# FIDO2AUTH_00211.net
KiCad netlist of a schematic drawn in EAGLE
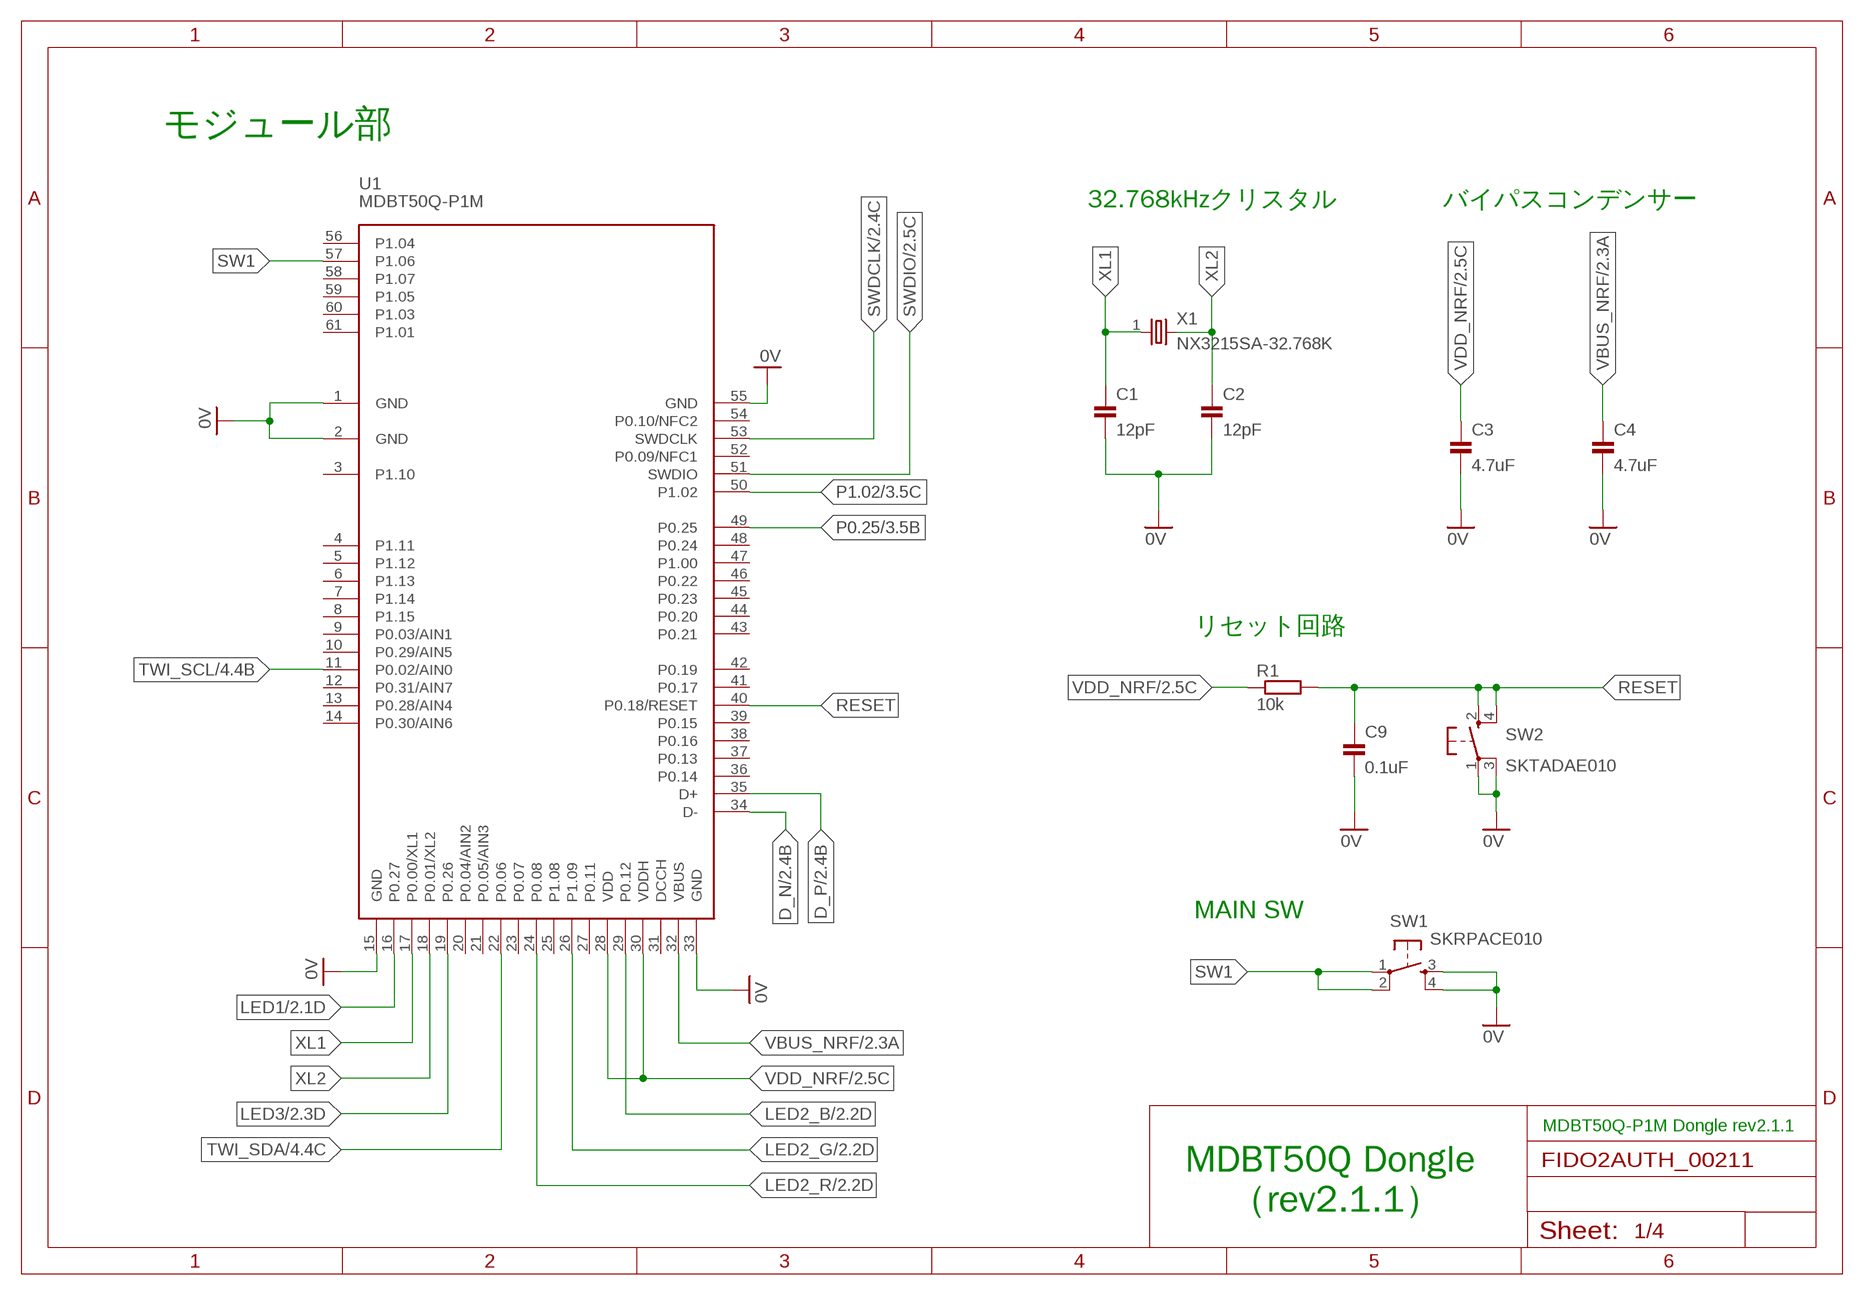
[diagram p0: schematic, sheet 1]
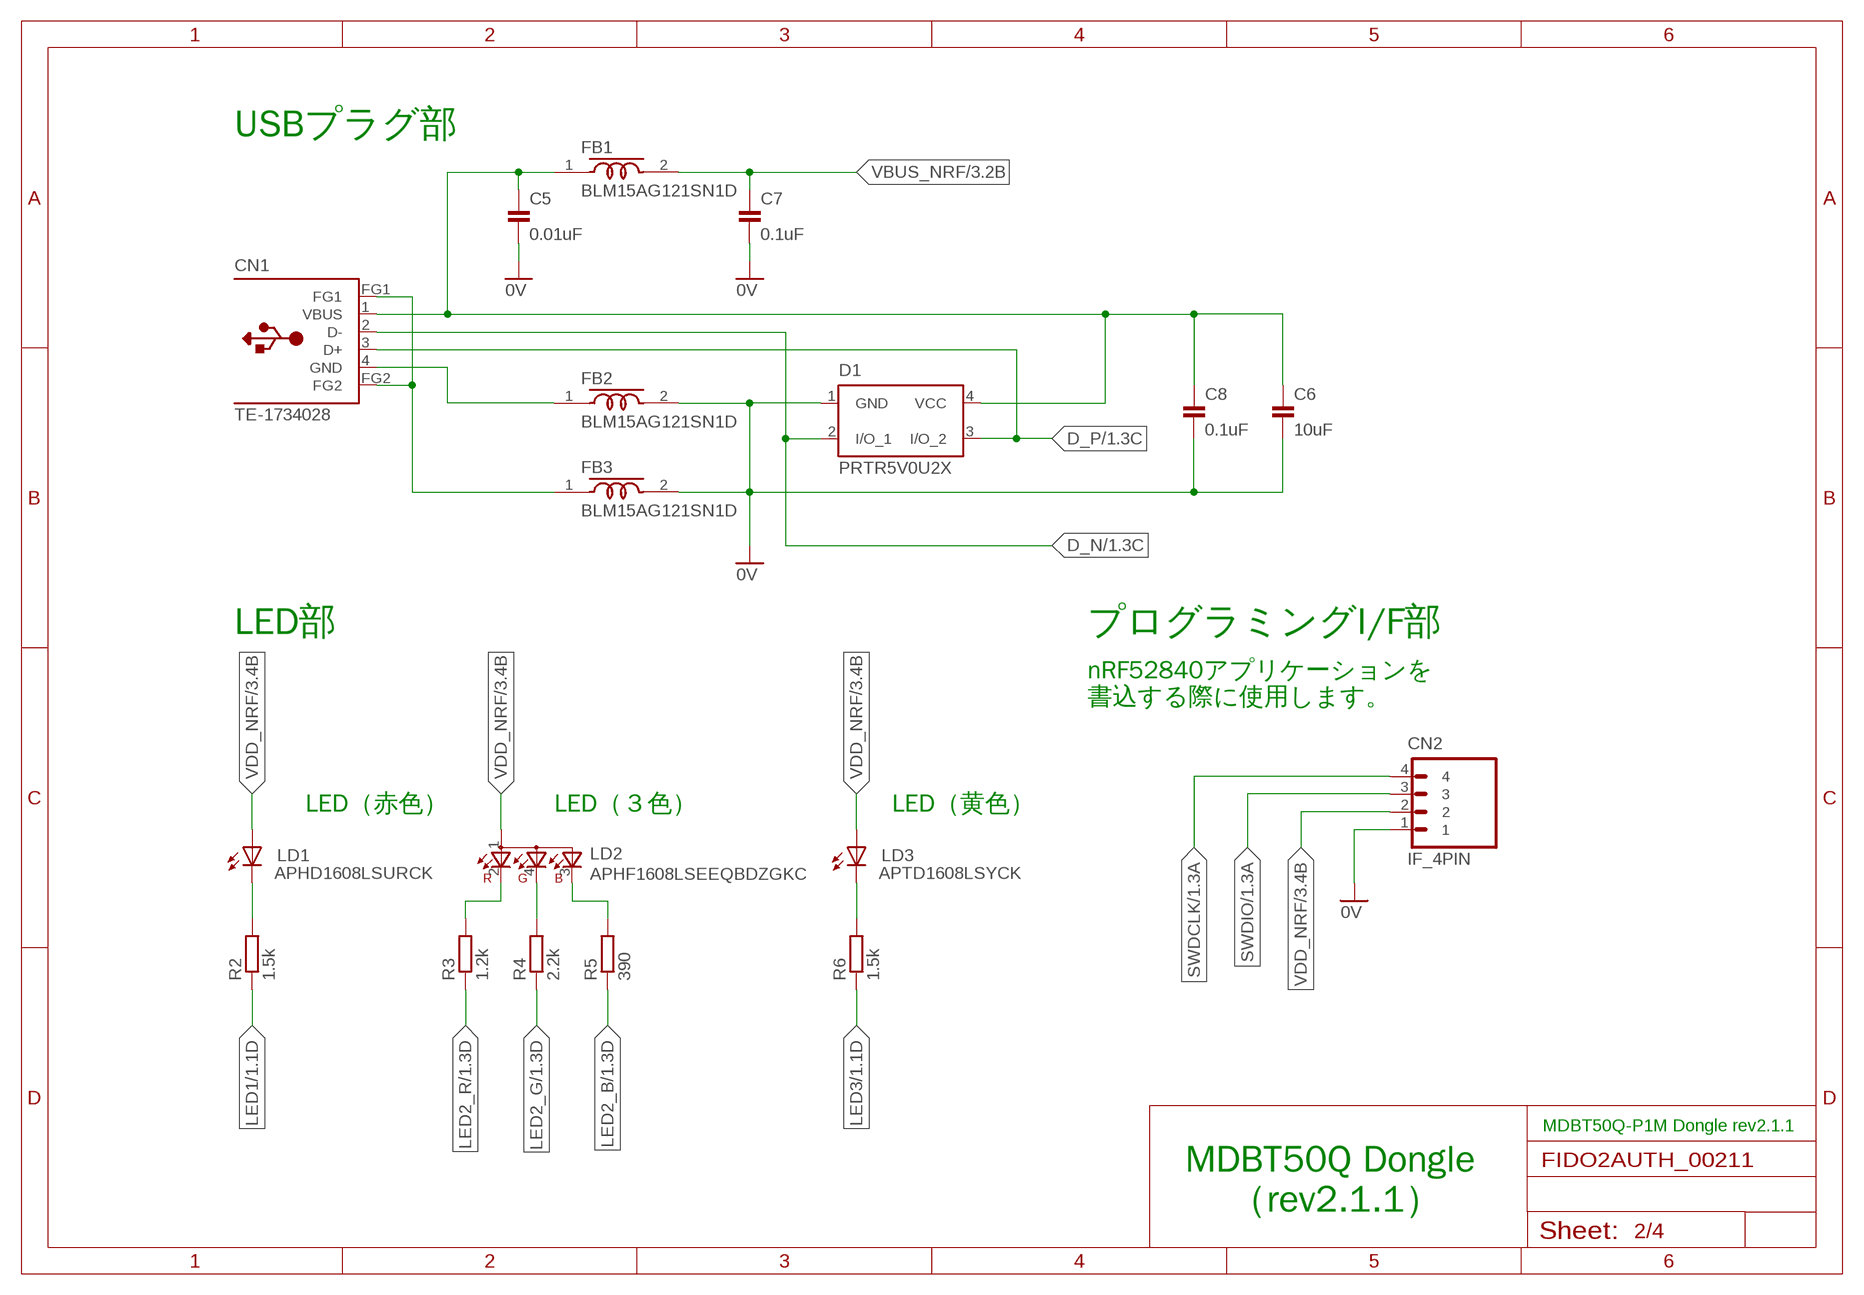
[diagram p1: schematic, sheet 2]
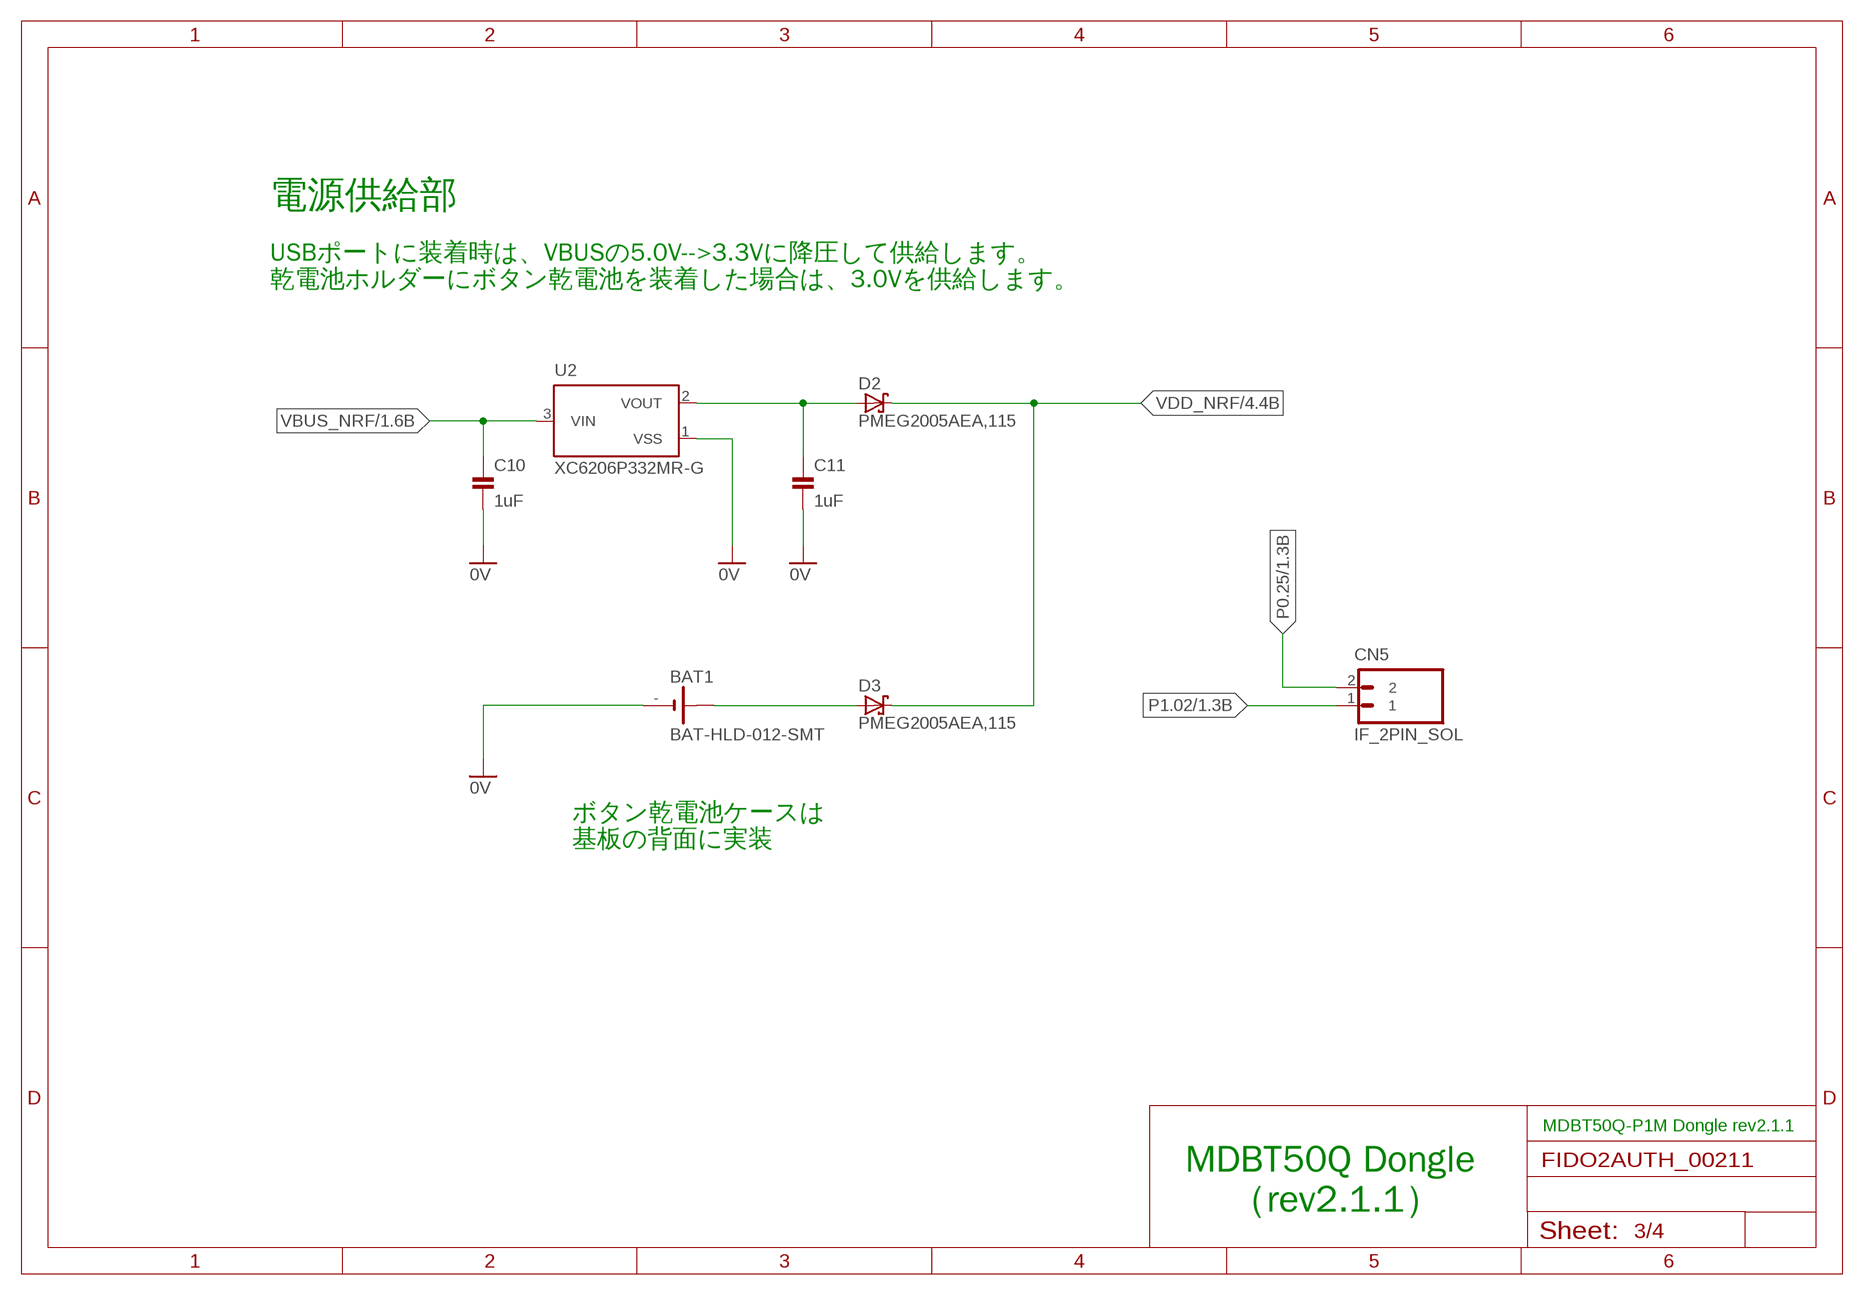
[diagram p2: schematic, sheet 3]
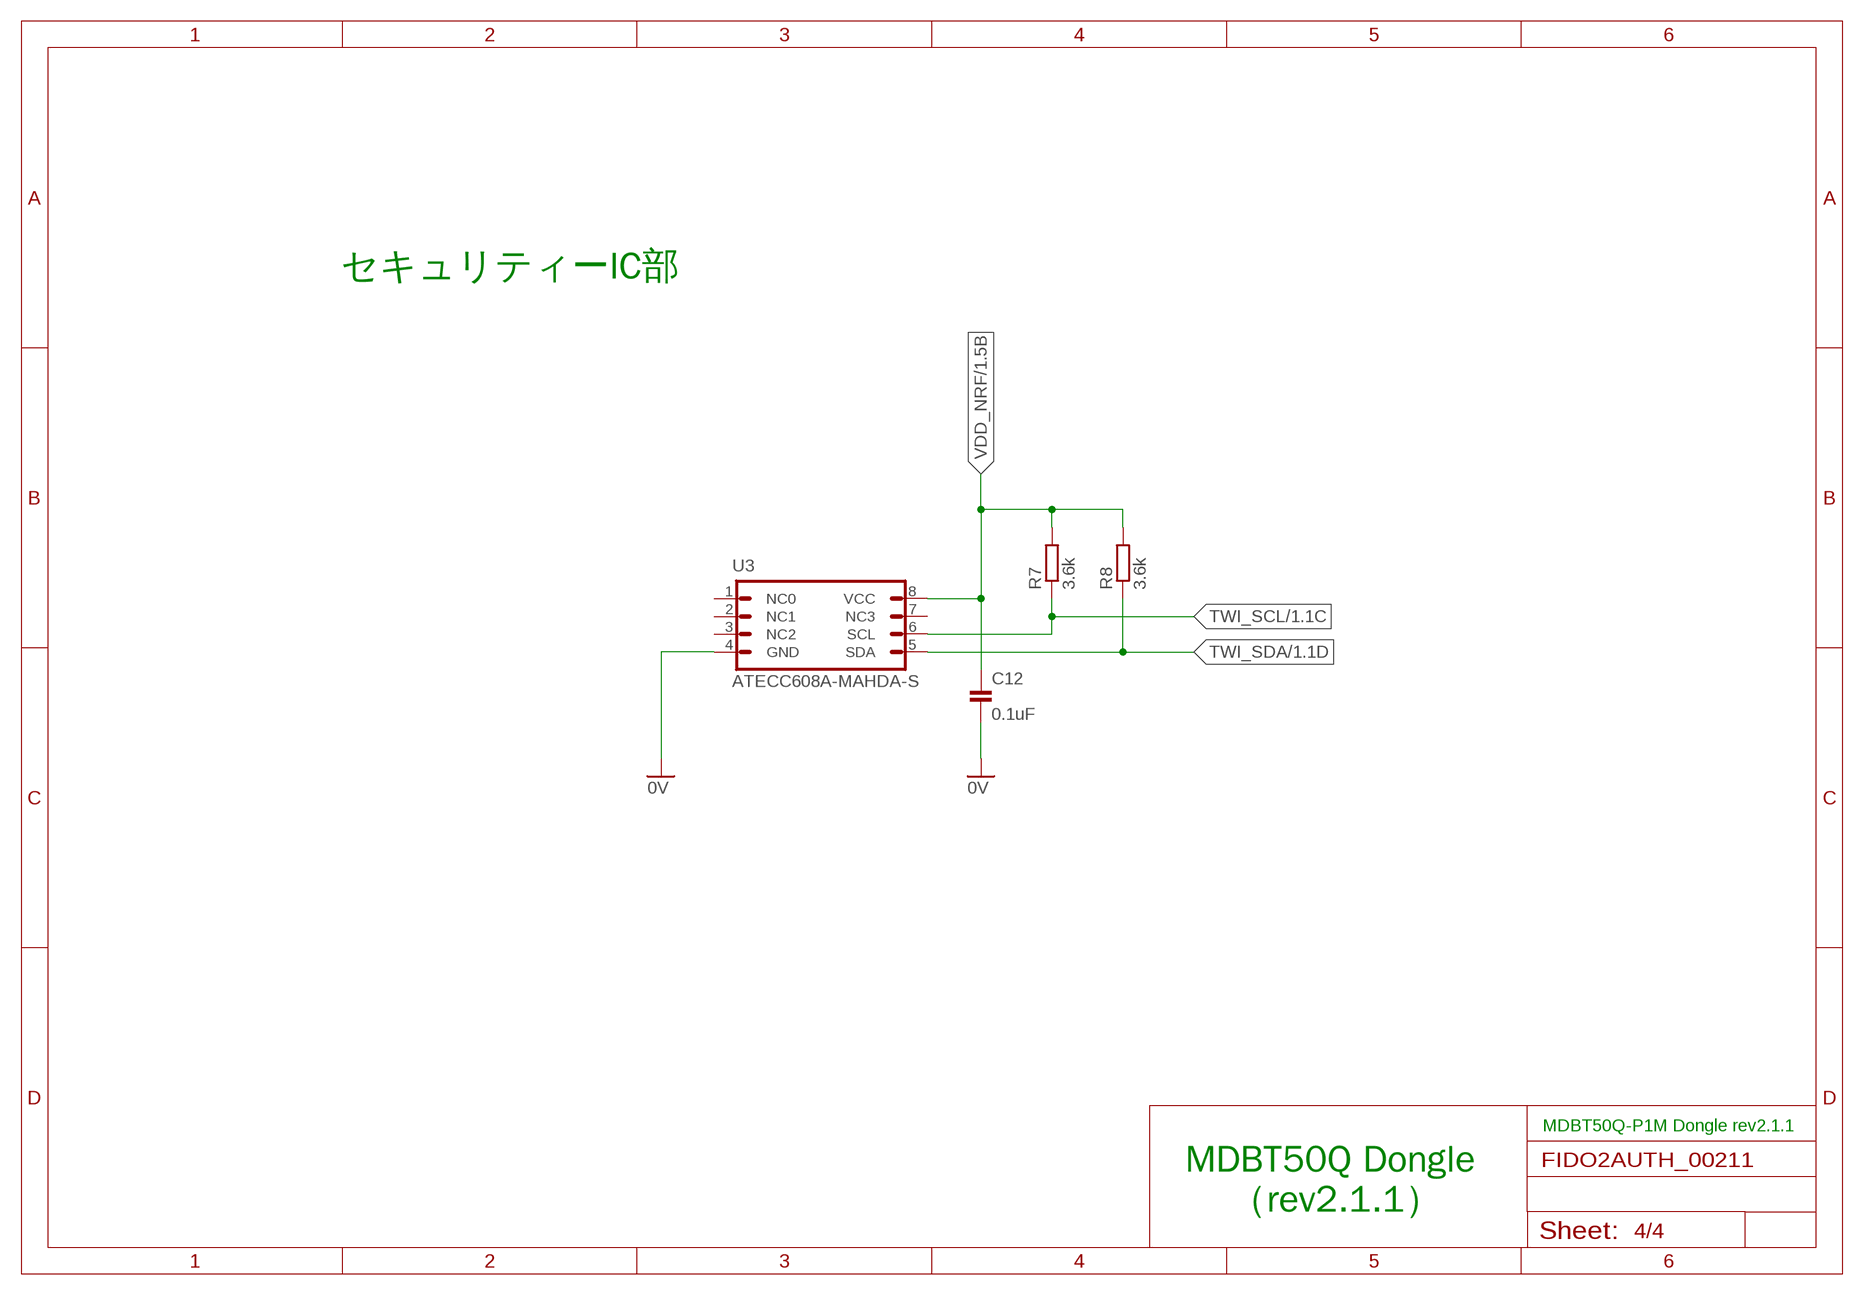
[diagram p3: schematic, sheet 4]

(export (version "E")
  (design (tool "Eeschema 10.0.6"))
  (components
    (comp (ref "C5")
      (value "0.01uF")
      (footprint "eagle-import:C0402K")
      (libsource (lib "eagle-import") (part "CAP_0402K"))
    )
    (comp (ref "C6")
      (value "10uF")
      (footprint "eagle-import:C0603K")
      (libsource (lib "eagle-import") (part "CAP_0603"))
    )
    (comp (ref "C7")
      (value "0.1uF")
      (footprint "eagle-import:C0402K")
      (libsource (lib "eagle-import") (part "CAP_0402K"))
    )
    (comp (ref "C8")
      (value "0.1uF")
      (footprint "eagle-import:C0402K")
      (libsource (lib "eagle-import") (part "CAP_0402K"))
    )
    (comp (ref "CN1")
      (value "TE-1734028")
      (footprint "eagle-import:TE-1734028")
      (libsource (lib "eagle-import") (part "TE-1734028"))
    )
    (comp (ref "CN2")
      (value "IF_4PIN")
      (footprint "eagle-import:HEADER_4PIN")
      (libsource (lib "eagle-import") (part "IF_4PIN"))
    )
    (comp (ref "D1")
      (value "PRTR5V0U2X")
      (footprint "eagle-import:SOT143B")
      (libsource (lib "eagle-import") (part "PRTR5V0U2X"))
    )
    (comp (ref "FB1")
      (value "BLM15AG121SN1D")
      (footprint "eagle-import:C0402K")
      (libsource (lib "eagle-import") (part "BLM15AG121SN1D"))
    )
    (comp (ref "FB2")
      (value "BLM15AG121SN1D")
      (footprint "eagle-import:C0402K")
      (libsource (lib "eagle-import") (part "BLM15AG121SN1D"))
    )
    (comp (ref "FB3")
      (value "BLM15AG121SN1D")
      (footprint "eagle-import:C0402K")
      (libsource (lib "eagle-import") (part "BLM15AG121SN1D"))
    )
    (comp (ref "LD1")
      (value "APHD1608LSURCK")
      (footprint "eagle-import:CHIPLED_0603")
      (libsource (lib "eagle-import") (part "APHD1608LSURCK"))
    )
    (comp (ref "LD2")
      (value "APHF1608LSEEQBDZGKC")
      (footprint "eagle-import:APHF1608LSEEQBDZGKC")
      (libsource (lib "eagle-import") (part "APHF1608LSEEQBDZGKC"))
    )
    (comp (ref "LD3")
      (value "APTD1608LSYCK")
      (footprint "eagle-import:CHIPLED_0603")
      (libsource (lib "eagle-import") (part "APTD1608LSYCK"))
    )
    (comp (ref "R2")
      (value "1.5k")
      (footprint "eagle-import:R0402")
      (libsource (lib "eagle-import") (part "RESISTOR_0402"))
    )
    (comp (ref "R3")
      (value "1.2k")
      (footprint "eagle-import:R0402")
      (libsource (lib "eagle-import") (part "RESISTOR_0402"))
    )
    (comp (ref "R4")
      (value "2.2k")
      (footprint "eagle-import:R0402")
      (libsource (lib "eagle-import") (part "RESISTOR_0402"))
    )
    (comp (ref "R5")
      (value "390")
      (footprint "eagle-import:R0402")
      (libsource (lib "eagle-import") (part "RESISTOR_0402"))
    )
    (comp (ref "R6")
      (value "1.5k")
      (footprint "eagle-import:R0402")
      (libsource (lib "eagle-import") (part "RESISTOR_0402"))
    )
    (comp (ref "C12")
      (value "0.1uF")
      (footprint "eagle-import:C0402K")
      (libsource (lib "eagle-import") (part "CAP_0402K"))
    )
    (comp (ref "R7")
      (value "3.6k")
      (footprint "eagle-import:R0402")
      (libsource (lib "eagle-import") (part "RESISTOR_0402"))
    )
    (comp (ref "R8")
      (value "3.6k")
      (footprint "eagle-import:R0402")
      (libsource (lib "eagle-import") (part "RESISTOR_0402"))
    )
    (comp (ref "U3")
      (value "ATECC608A-MAHDA-S")
      (footprint "eagle-import:DFN-2X3")
      (libsource (lib "eagle-import") (part "ATECC608A-MAHDA-S"))
    )
    (comp (ref "C1")
      (value "12pF")
      (footprint "eagle-import:C0603K")
      (libsource (lib "eagle-import") (part "CAP_0603"))
    )
    (comp (ref "C2")
      (value "12pF")
      (footprint "eagle-import:C0603K")
      (libsource (lib "eagle-import") (part "CAP_0603"))
    )
    (comp (ref "C3")
      (value "4.7uF")
      (footprint "eagle-import:C0603K")
      (libsource (lib "eagle-import") (part "CAP_0603"))
    )
    (comp (ref "C4")
      (value "4.7uF")
      (footprint "eagle-import:C0603K")
      (libsource (lib "eagle-import") (part "CAP_0603"))
    )
    (comp (ref "C9")
      (value "0.1uF")
      (footprint "eagle-import:C0402K")
      (libsource (lib "eagle-import") (part "CAP_0402K"))
    )
    (comp (ref "R1")
      (value "10k")
      (footprint "eagle-import:R0402")
      (libsource (lib "eagle-import") (part "RESISTOR_0402"))
    )
    (comp (ref "SW1")
      (value "SKRPACE010")
      (footprint "eagle-import:SKRPACE010")
      (libsource (lib "eagle-import") (part "SKRPACE010"))
    )
    (comp (ref "SW2")
      (value "SKTADAE010")
      (footprint "eagle-import:SKTADAE010")
      (libsource (lib "eagle-import") (part "SKTADAE010"))
    )
    (comp (ref "U1")
      (value "MDBT50Q-P1M")
      (footprint "eagle-import:MDBT50Q-P1M")
      (libsource (lib "eagle-import") (part "MDBT50Q-P1M"))
    )
    (comp (ref "X1")
      (value "NX3215SA-32.768K")
      (footprint "eagle-import:NX3215")
      (libsource (lib "eagle-import") (part "NX3215SA-32.768K"))
    )
    (comp (ref "BAT1")
      (value "BAT-HLD-012-SMT")
      (footprint "eagle-import:BAT-HLD-012-SMT")
      (libsource (lib "eagle-import") (part "BAT-HLD-012-SMT"))
    )
    (comp (ref "C10")
      (value "1uF")
      (footprint "eagle-import:C0603K")
      (libsource (lib "eagle-import") (part "CAP_0603"))
    )
    (comp (ref "C11")
      (value "1uF")
      (footprint "eagle-import:C0603K")
      (libsource (lib "eagle-import") (part "CAP_0603"))
    )
    (comp (ref "CN5")
      (value "IF_2PIN_SOL")
      (footprint "eagle-import:SOLPAD_2PIN")
      (libsource (lib "eagle-import") (part "IF_2PIN_SOL"))
    )
    (comp (ref "D2")
      (value "PMEG2005AEA,115")
      (footprint "eagle-import:SOD323-W")
      (libsource (lib "eagle-import") (part "PMEG2005AEA,115"))
    )
    (comp (ref "D3")
      (value "PMEG2005AEA,115")
      (footprint "eagle-import:SOD323-W")
      (libsource (lib "eagle-import") (part "PMEG2005AEA,115"))
    )
    (comp (ref "U2")
      (value "XC6206P332MR-G")
      (footprint "eagle-import:SOT23")
      (libsource (lib "eagle-import") (part "XC6206P332MR-G"))
    )
  )
  (nets
    (net (code "1") (name "0V") (class "Default")
      (node (ref "BAT1") (pin "-") (pinfunction "-_-") (pintype "passive"))
      (node (ref "C1") (pin "2") (pinfunction "2_2") (pintype "passive"))
      (node (ref "C10") (pin "2") (pinfunction "2_2") (pintype "passive"))
      (node (ref "C11") (pin "2") (pinfunction "2_2") (pintype "passive"))
      (node (ref "C12") (pin "2") (pinfunction "2_2") (pintype "passive"))
      (node (ref "C2") (pin "2") (pinfunction "2_2") (pintype "passive"))
      (node (ref "C3") (pin "2") (pinfunction "2_2") (pintype "passive"))
      (node (ref "C4") (pin "2") (pinfunction "2_2") (pintype "passive"))
      (node (ref "C5") (pin "2") (pinfunction "2_2") (pintype "passive"))
      (node (ref "C6") (pin "2") (pinfunction "2_2") (pintype "passive"))
      (node (ref "C7") (pin "2") (pinfunction "2_2") (pintype "passive"))
      (node (ref "C8") (pin "2") (pinfunction "2_2") (pintype "passive"))
      (node (ref "C9") (pin "2") (pinfunction "2_2") (pintype "passive"))
      (node (ref "CN2") (pin "1") (pinfunction "1_1") (pintype "passive"))
      (node (ref "D1") (pin "1") (pinfunction "GND_1") (pintype "passive"))
      (node (ref "FB2") (pin "2") (pinfunction "2_2") (pintype "passive"))
      (node (ref "FB3") (pin "2") (pinfunction "2_2") (pintype "passive"))
      (node (ref "SW1") (pin "3") (pinfunction "S_3") (pintype "passive"))
      (node (ref "SW1") (pin "4") (pinfunction "S1_4") (pintype "passive"))
      (node (ref "SW2") (pin "1") (pinfunction "P_1") (pintype "passive"))
      (node (ref "SW2") (pin "3") (pinfunction "P1_3") (pintype "passive"))
      (node (ref "U1") (pin "1") (pinfunction "GND_1") (pintype "bidirectional"))
      (node (ref "U1") (pin "15") (pinfunction "GND_15") (pintype "bidirectional"))
      (node (ref "U1") (pin "2") (pinfunction "GND_2") (pintype "bidirectional"))
      (node (ref "U1") (pin "33") (pinfunction "GND_33") (pintype "bidirectional"))
      (node (ref "U1") (pin "55") (pinfunction "GND_55") (pintype "bidirectional"))
      (node (ref "U2") (pin "1") (pinfunction "VSS_1") (pintype "passive"))
      (node (ref "U3") (pin "4") (pinfunction "GND_4") (pintype "passive"))
    )
    (net (code "2") (name "D_N") (class "Default")
      (node (ref "CN1") (pin "2") (pinfunction "D-_2") (pintype "bidirectional"))
      (node (ref "D1") (pin "2") (pinfunction "I/O_1_2") (pintype "bidirectional"))
      (node (ref "U1") (pin "34") (pinfunction "D-_34") (pintype "bidirectional"))
    )
    (net (code "3") (name "D_P") (class "Default")
      (node (ref "CN1") (pin "3") (pinfunction "D+_3") (pintype "bidirectional"))
      (node (ref "D1") (pin "3") (pinfunction "I/O_2_3") (pintype "bidirectional"))
      (node (ref "U1") (pin "35") (pinfunction "D+_35") (pintype "bidirectional"))
    )
    (net (code "4") (name "LED1") (class "Default")
      (node (ref "R2") (pin "1") (pinfunction "1_1") (pintype "passive"))
      (node (ref "U1") (pin "16") (pinfunction "P0.27_16") (pintype "bidirectional"))
    )
    (net (code "5") (name "LED2_B") (class "Default")
      (node (ref "R5") (pin "1") (pinfunction "1_1") (pintype "passive"))
      (node (ref "U1") (pin "29") (pinfunction "P0.12_29") (pintype "bidirectional"))
    )
    (net (code "6") (name "LED2_G") (class "Default")
      (node (ref "R4") (pin "1") (pinfunction "1_1") (pintype "passive"))
      (node (ref "U1") (pin "26") (pinfunction "P1.09_26") (pintype "bidirectional"))
    )
    (net (code "7") (name "LED2_R") (class "Default")
      (node (ref "R3") (pin "1") (pinfunction "1_1") (pintype "passive"))
      (node (ref "U1") (pin "24") (pinfunction "P0.08_24") (pintype "bidirectional"))
    )
    (net (code "8") (name "LED3") (class "Default")
      (node (ref "R6") (pin "1") (pinfunction "1_1") (pintype "passive"))
      (node (ref "U1") (pin "19") (pinfunction "P0.26_19") (pintype "bidirectional"))
    )
    (net (code "9") (name "Net-(BAT1-+)") (class "Default")
      (node (ref "BAT1") (pin "+@1") (pinfunction "+_+@1") (pintype "passive"))
      (node (ref "D3") (pin "A") (pinfunction "A_A") (pintype "passive"))
    )
    (net (code "10") (name "Net-(CN1-GND)") (class "Default")
      (node (ref "CN1") (pin "4") (pinfunction "GND_4") (pintype "passive"))
      (node (ref "FB2") (pin "1") (pinfunction "1_1") (pintype "passive"))
    )
    (net (code "11") (name "Net-(CN1-PadFG1)") (class "Default")
      (node (ref "CN1") (pin "FG1") (pinfunction "FG1_FG1") (pintype "passive"))
      (node (ref "CN1") (pin "FG2") (pinfunction "FG2_FG2") (pintype "passive"))
      (node (ref "FB3") (pin "1") (pinfunction "1_1") (pintype "passive"))
    )
    (net (code "12") (name "Net-(CN1-VBUS)") (class "Default")
      (node (ref "C5") (pin "1") (pinfunction "1_1") (pintype "passive"))
      (node (ref "C6") (pin "1") (pinfunction "1_1") (pintype "passive"))
      (node (ref "C8") (pin "1") (pinfunction "1_1") (pintype "passive"))
      (node (ref "CN1") (pin "1") (pinfunction "VBUS_1") (pintype "passive"))
      (node (ref "D1") (pin "4") (pinfunction "VCC_4") (pintype "passive"))
      (node (ref "FB1") (pin "1") (pinfunction "1_1") (pintype "passive"))
    )
    (net (code "13") (name "Net-(LD1-PadC)") (class "Default")
      (node (ref "LD1") (pin "C") (pinfunction "C_C") (pintype "passive"))
      (node (ref "R2") (pin "2") (pinfunction "2_2") (pintype "passive"))
    )
    (net (code "14") (name "Net-(LD2-CBLUE)") (class "Default")
      (node (ref "LD2") (pin "3") (pinfunction "CBLUE_3") (pintype "passive"))
      (node (ref "R5") (pin "2") (pinfunction "2_2") (pintype "passive"))
    )
    (net (code "15") (name "Net-(LD2-CGREEN)") (class "Default")
      (node (ref "LD2") (pin "4") (pinfunction "CGREEN_4") (pintype "passive"))
      (node (ref "R4") (pin "2") (pinfunction "2_2") (pintype "passive"))
    )
    (net (code "16") (name "Net-(LD2-CRED)") (class "Default")
      (node (ref "LD2") (pin "2") (pinfunction "CRED_2") (pintype "passive"))
      (node (ref "R3") (pin "2") (pinfunction "2_2") (pintype "passive"))
    )
    (net (code "17") (name "Net-(LD3-PadC)") (class "Default")
      (node (ref "LD3") (pin "C") (pinfunction "C_C") (pintype "passive"))
      (node (ref "R6") (pin "2") (pinfunction "2_2") (pintype "passive"))
    )
    (net (code "18") (name "Net-(U2-VOUT)") (class "Default")
      (node (ref "C11") (pin "1") (pinfunction "1_1") (pintype "passive"))
      (node (ref "D2") (pin "A") (pinfunction "A_A") (pintype "passive"))
      (node (ref "U2") (pin "2") (pinfunction "VOUT_2") (pintype "passive"))
    )
    (net (code "19") (name "P0.25") (class "Default")
      (node (ref "CN5") (pin "2") (pinfunction "2_2") (pintype "passive"))
      (node (ref "U1") (pin "49") (pinfunction "P0.25_49") (pintype "bidirectional"))
    )
    (net (code "20") (name "P1.02") (class "Default")
      (node (ref "CN5") (pin "1") (pinfunction "1_1") (pintype "passive"))
      (node (ref "U1") (pin "50") (pinfunction "P1.02_50") (pintype "bidirectional"))
    )
    (net (code "21") (name "RESET") (class "Default")
      (node (ref "C9") (pin "1") (pinfunction "1_1") (pintype "passive"))
      (node (ref "R1") (pin "2") (pinfunction "2_2") (pintype "passive"))
      (node (ref "SW2") (pin "2") (pinfunction "S_2") (pintype "passive"))
      (node (ref "SW2") (pin "4") (pinfunction "S1_4") (pintype "passive"))
      (node (ref "U1") (pin "40") (pinfunction "P0.18/RESET_40") (pintype "bidirectional"))
    )
    (net (code "22") (name "SW1") (class "Default")
      (node (ref "SW1") (pin "1") (pinfunction "P_1") (pintype "passive"))
      (node (ref "SW1") (pin "2") (pinfunction "P1_2") (pintype "passive"))
      (node (ref "U1") (pin "57") (pinfunction "P1.06_57") (pintype "bidirectional"))
    )
    (net (code "23") (name "SWDCLK") (class "Default")
      (node (ref "CN2") (pin "4") (pinfunction "4_4") (pintype "passive"))
      (node (ref "U1") (pin "53") (pinfunction "SWDCLK_53") (pintype "bidirectional"))
    )
    (net (code "24") (name "SWDIO") (class "Default")
      (node (ref "CN2") (pin "3") (pinfunction "3_3") (pintype "passive"))
      (node (ref "U1") (pin "51") (pinfunction "SWDIO_51") (pintype "bidirectional"))
    )
    (net (code "25") (name "TWI_SCL") (class "Default")
      (node (ref "R7") (pin "1") (pinfunction "1_1") (pintype "passive"))
      (node (ref "U1") (pin "11") (pinfunction "P0.02/AIN0_11") (pintype "bidirectional"))
      (node (ref "U3") (pin "6") (pinfunction "SCL_6") (pintype "bidirectional"))
    )
    (net (code "26") (name "TWI_SDA") (class "Default")
      (node (ref "R8") (pin "1") (pinfunction "1_1") (pintype "passive"))
      (node (ref "U1") (pin "22") (pinfunction "P0.06_22") (pintype "bidirectional"))
      (node (ref "U3") (pin "5") (pinfunction "SDA_5") (pintype "bidirectional"))
    )
    (net (code "27") (name "VBUS_NRF") (class "Default")
      (node (ref "C10") (pin "1") (pinfunction "1_1") (pintype "passive"))
      (node (ref "C4") (pin "1") (pinfunction "1_1") (pintype "passive"))
      (node (ref "C7") (pin "1") (pinfunction "1_1") (pintype "passive"))
      (node (ref "FB1") (pin "2") (pinfunction "2_2") (pintype "passive"))
      (node (ref "U1") (pin "32") (pinfunction "VBUS_32") (pintype "bidirectional"))
      (node (ref "U2") (pin "3") (pinfunction "VIN_3") (pintype "passive"))
    )
    (net (code "28") (name "VDD_NRF") (class "Default")
      (node (ref "C12") (pin "1") (pinfunction "1_1") (pintype "passive"))
      (node (ref "C3") (pin "1") (pinfunction "1_1") (pintype "passive"))
      (node (ref "CN2") (pin "2") (pinfunction "2_2") (pintype "passive"))
      (node (ref "D2") (pin "C") (pinfunction "C_C") (pintype "passive"))
      (node (ref "D3") (pin "C") (pinfunction "C_C") (pintype "passive"))
      (node (ref "LD1") (pin "A") (pinfunction "A_A") (pintype "passive"))
      (node (ref "LD2") (pin "1") (pinfunction "A_1") (pintype "passive"))
      (node (ref "LD3") (pin "A") (pinfunction "A_A") (pintype "passive"))
      (node (ref "R1") (pin "1") (pinfunction "1_1") (pintype "passive"))
      (node (ref "R7") (pin "2") (pinfunction "2_2") (pintype "passive"))
      (node (ref "R8") (pin "2") (pinfunction "2_2") (pintype "passive"))
      (node (ref "U1") (pin "28") (pinfunction "VDD_28") (pintype "bidirectional"))
      (node (ref "U1") (pin "30") (pinfunction "VDDH_30") (pintype "bidirectional"))
      (node (ref "U3") (pin "8") (pinfunction "VCC_8") (pintype "passive"))
    )
    (net (code "29") (name "XL1") (class "Default")
      (node (ref "C1") (pin "1") (pinfunction "1_1") (pintype "passive"))
      (node (ref "U1") (pin "17") (pinfunction "P0.00/XL1_17") (pintype "bidirectional"))
      (node (ref "X1") (pin "1") (pinfunction "1_1") (pintype "passive"))
    )
    (net (code "30") (name "XL2") (class "Default")
      (node (ref "C2") (pin "1") (pinfunction "1_1") (pintype "passive"))
      (node (ref "U1") (pin "18") (pinfunction "P0.01/XL2_18") (pintype "bidirectional"))
      (node (ref "X1") (pin "2") (pinfunction "2_2") (pintype "passive"))
    )
    (net (code "31") (name "unconnected-(U1-DCCH-Pad31)") (class "Default")
      (node (ref "U1") (pin "31") (pinfunction "DCCH_31") (pintype "bidirectional"))
    )
    (net (code "32") (name "unconnected-(U1-P0.03{slash}AIN1-Pad9)") (class "Default")
      (node (ref "U1") (pin "9") (pinfunction "P0.03/AIN1_9") (pintype "bidirectional"))
    )
    (net (code "33") (name "unconnected-(U1-P0.04{slash}AIN2-Pad20)") (class "Default")
      (node (ref "U1") (pin "20") (pinfunction "P0.04/AIN2_20") (pintype "bidirectional"))
    )
    (net (code "34") (name "unconnected-(U1-P0.05{slash}AIN3-Pad21)") (class "Default")
      (node (ref "U1") (pin "21") (pinfunction "P0.05/AIN3_21") (pintype "bidirectional"))
    )
    (net (code "35") (name "unconnected-(U1-P0.07-Pad23)") (class "Default")
      (node (ref "U1") (pin "23") (pinfunction "P0.07_23") (pintype "bidirectional"))
    )
    (net (code "36") (name "unconnected-(U1-P0.09{slash}NFC1-Pad52)") (class "Default")
      (node (ref "U1") (pin "52") (pinfunction "P0.09/NFC1_52") (pintype "bidirectional"))
    )
    (net (code "37") (name "unconnected-(U1-P0.10{slash}NFC2-Pad54)") (class "Default")
      (node (ref "U1") (pin "54") (pinfunction "P0.10/NFC2_54") (pintype "bidirectional"))
    )
    (net (code "38") (name "unconnected-(U1-P0.11-Pad27)") (class "Default")
      (node (ref "U1") (pin "27") (pinfunction "P0.11_27") (pintype "bidirectional"))
    )
    (net (code "39") (name "unconnected-(U1-P0.13-Pad37)") (class "Default")
      (node (ref "U1") (pin "37") (pinfunction "P0.13_37") (pintype "bidirectional"))
    )
    (net (code "40") (name "unconnected-(U1-P0.14-Pad36)") (class "Default")
      (node (ref "U1") (pin "36") (pinfunction "P0.14_36") (pintype "bidirectional"))
    )
    (net (code "41") (name "unconnected-(U1-P0.15-Pad39)") (class "Default")
      (node (ref "U1") (pin "39") (pinfunction "P0.15_39") (pintype "bidirectional"))
    )
    (net (code "42") (name "unconnected-(U1-P0.16-Pad38)") (class "Default")
      (node (ref "U1") (pin "38") (pinfunction "P0.16_38") (pintype "bidirectional"))
    )
    (net (code "43") (name "unconnected-(U1-P0.17-Pad41)") (class "Default")
      (node (ref "U1") (pin "41") (pinfunction "P0.17_41") (pintype "bidirectional"))
    )
    (net (code "44") (name "unconnected-(U1-P0.19-Pad42)") (class "Default")
      (node (ref "U1") (pin "42") (pinfunction "P0.19_42") (pintype "bidirectional"))
    )
    (net (code "45") (name "unconnected-(U1-P0.20-Pad44)") (class "Default")
      (node (ref "U1") (pin "44") (pinfunction "P0.20_44") (pintype "bidirectional"))
    )
    (net (code "46") (name "unconnected-(U1-P0.21-Pad43)") (class "Default")
      (node (ref "U1") (pin "43") (pinfunction "P0.21_43") (pintype "bidirectional"))
    )
    (net (code "47") (name "unconnected-(U1-P0.22-Pad46)") (class "Default")
      (node (ref "U1") (pin "46") (pinfunction "P0.22_46") (pintype "bidirectional"))
    )
    (net (code "48") (name "unconnected-(U1-P0.23-Pad45)") (class "Default")
      (node (ref "U1") (pin "45") (pinfunction "P0.23_45") (pintype "bidirectional"))
    )
    (net (code "49") (name "unconnected-(U1-P0.24-Pad48)") (class "Default")
      (node (ref "U1") (pin "48") (pinfunction "P0.24_48") (pintype "bidirectional"))
    )
    (net (code "50") (name "unconnected-(U1-P0.28{slash}AIN4-Pad13)") (class "Default")
      (node (ref "U1") (pin "13") (pinfunction "P0.28/AIN4_13") (pintype "bidirectional"))
    )
    (net (code "51") (name "unconnected-(U1-P0.29{slash}AIN5-Pad10)") (class "Default")
      (node (ref "U1") (pin "10") (pinfunction "P0.29/AIN5_10") (pintype "bidirectional"))
    )
    (net (code "52") (name "unconnected-(U1-P0.30{slash}AIN6-Pad14)") (class "Default")
      (node (ref "U1") (pin "14") (pinfunction "P0.30/AIN6_14") (pintype "bidirectional"))
    )
    (net (code "53") (name "unconnected-(U1-P0.31{slash}AIN7-Pad12)") (class "Default")
      (node (ref "U1") (pin "12") (pinfunction "P0.31/AIN7_12") (pintype "bidirectional"))
    )
    (net (code "54") (name "unconnected-(U1-P1.00-Pad47)") (class "Default")
      (node (ref "U1") (pin "47") (pinfunction "P1.00_47") (pintype "bidirectional"))
    )
    (net (code "55") (name "unconnected-(U1-P1.01-Pad61)") (class "Default")
      (node (ref "U1") (pin "61") (pinfunction "P1.01_61") (pintype "bidirectional"))
    )
    (net (code "56") (name "unconnected-(U1-P1.03-Pad60)") (class "Default")
      (node (ref "U1") (pin "60") (pinfunction "P1.03_60") (pintype "bidirectional"))
    )
    (net (code "57") (name "unconnected-(U1-P1.04-Pad56)") (class "Default")
      (node (ref "U1") (pin "56") (pinfunction "P1.04_56") (pintype "bidirectional"))
    )
    (net (code "58") (name "unconnected-(U1-P1.05-Pad59)") (class "Default")
      (node (ref "U1") (pin "59") (pinfunction "P1.05_59") (pintype "bidirectional"))
    )
    (net (code "59") (name "unconnected-(U1-P1.07-Pad58)") (class "Default")
      (node (ref "U1") (pin "58") (pinfunction "P1.07_58") (pintype "bidirectional"))
    )
    (net (code "60") (name "unconnected-(U1-P1.08-Pad25)") (class "Default")
      (node (ref "U1") (pin "25") (pinfunction "P1.08_25") (pintype "bidirectional"))
    )
    (net (code "61") (name "unconnected-(U1-P1.10-Pad3)") (class "Default")
      (node (ref "U1") (pin "3") (pinfunction "P1.10_3") (pintype "bidirectional"))
    )
    (net (code "62") (name "unconnected-(U1-P1.11-Pad4)") (class "Default")
      (node (ref "U1") (pin "4") (pinfunction "P1.11_4") (pintype "bidirectional"))
    )
    (net (code "63") (name "unconnected-(U1-P1.12-Pad5)") (class "Default")
      (node (ref "U1") (pin "5") (pinfunction "P1.12_5") (pintype "bidirectional"))
    )
    (net (code "64") (name "unconnected-(U1-P1.13-Pad6)") (class "Default")
      (node (ref "U1") (pin "6") (pinfunction "P1.13_6") (pintype "bidirectional"))
    )
    (net (code "65") (name "unconnected-(U1-P1.14-Pad7)") (class "Default")
      (node (ref "U1") (pin "7") (pinfunction "P1.14_7") (pintype "bidirectional"))
    )
    (net (code "66") (name "unconnected-(U1-P1.15-Pad8)") (class "Default")
      (node (ref "U1") (pin "8") (pinfunction "P1.15_8") (pintype "bidirectional"))
    )
    (net (code "67") (name "unconnected-(U3-NC0-Pad1)") (class "Default")
      (node (ref "U3") (pin "1") (pinfunction "NC0_1") (pintype "passive"))
    )
    (net (code "68") (name "unconnected-(U3-NC1-Pad2)") (class "Default")
      (node (ref "U3") (pin "2") (pinfunction "NC1_2") (pintype "passive"))
    )
    (net (code "69") (name "unconnected-(U3-NC2-Pad3)") (class "Default")
      (node (ref "U3") (pin "3") (pinfunction "NC2_3") (pintype "passive"))
    )
    (net (code "70") (name "unconnected-(U3-NC3-Pad7)") (class "Default")
      (node (ref "U3") (pin "7") (pinfunction "NC3_7") (pintype "passive"))
    )
  )
)
